# dogs102_3_3v_v0_5.net
KiCad netlist of a schematic drawn in EAGLE
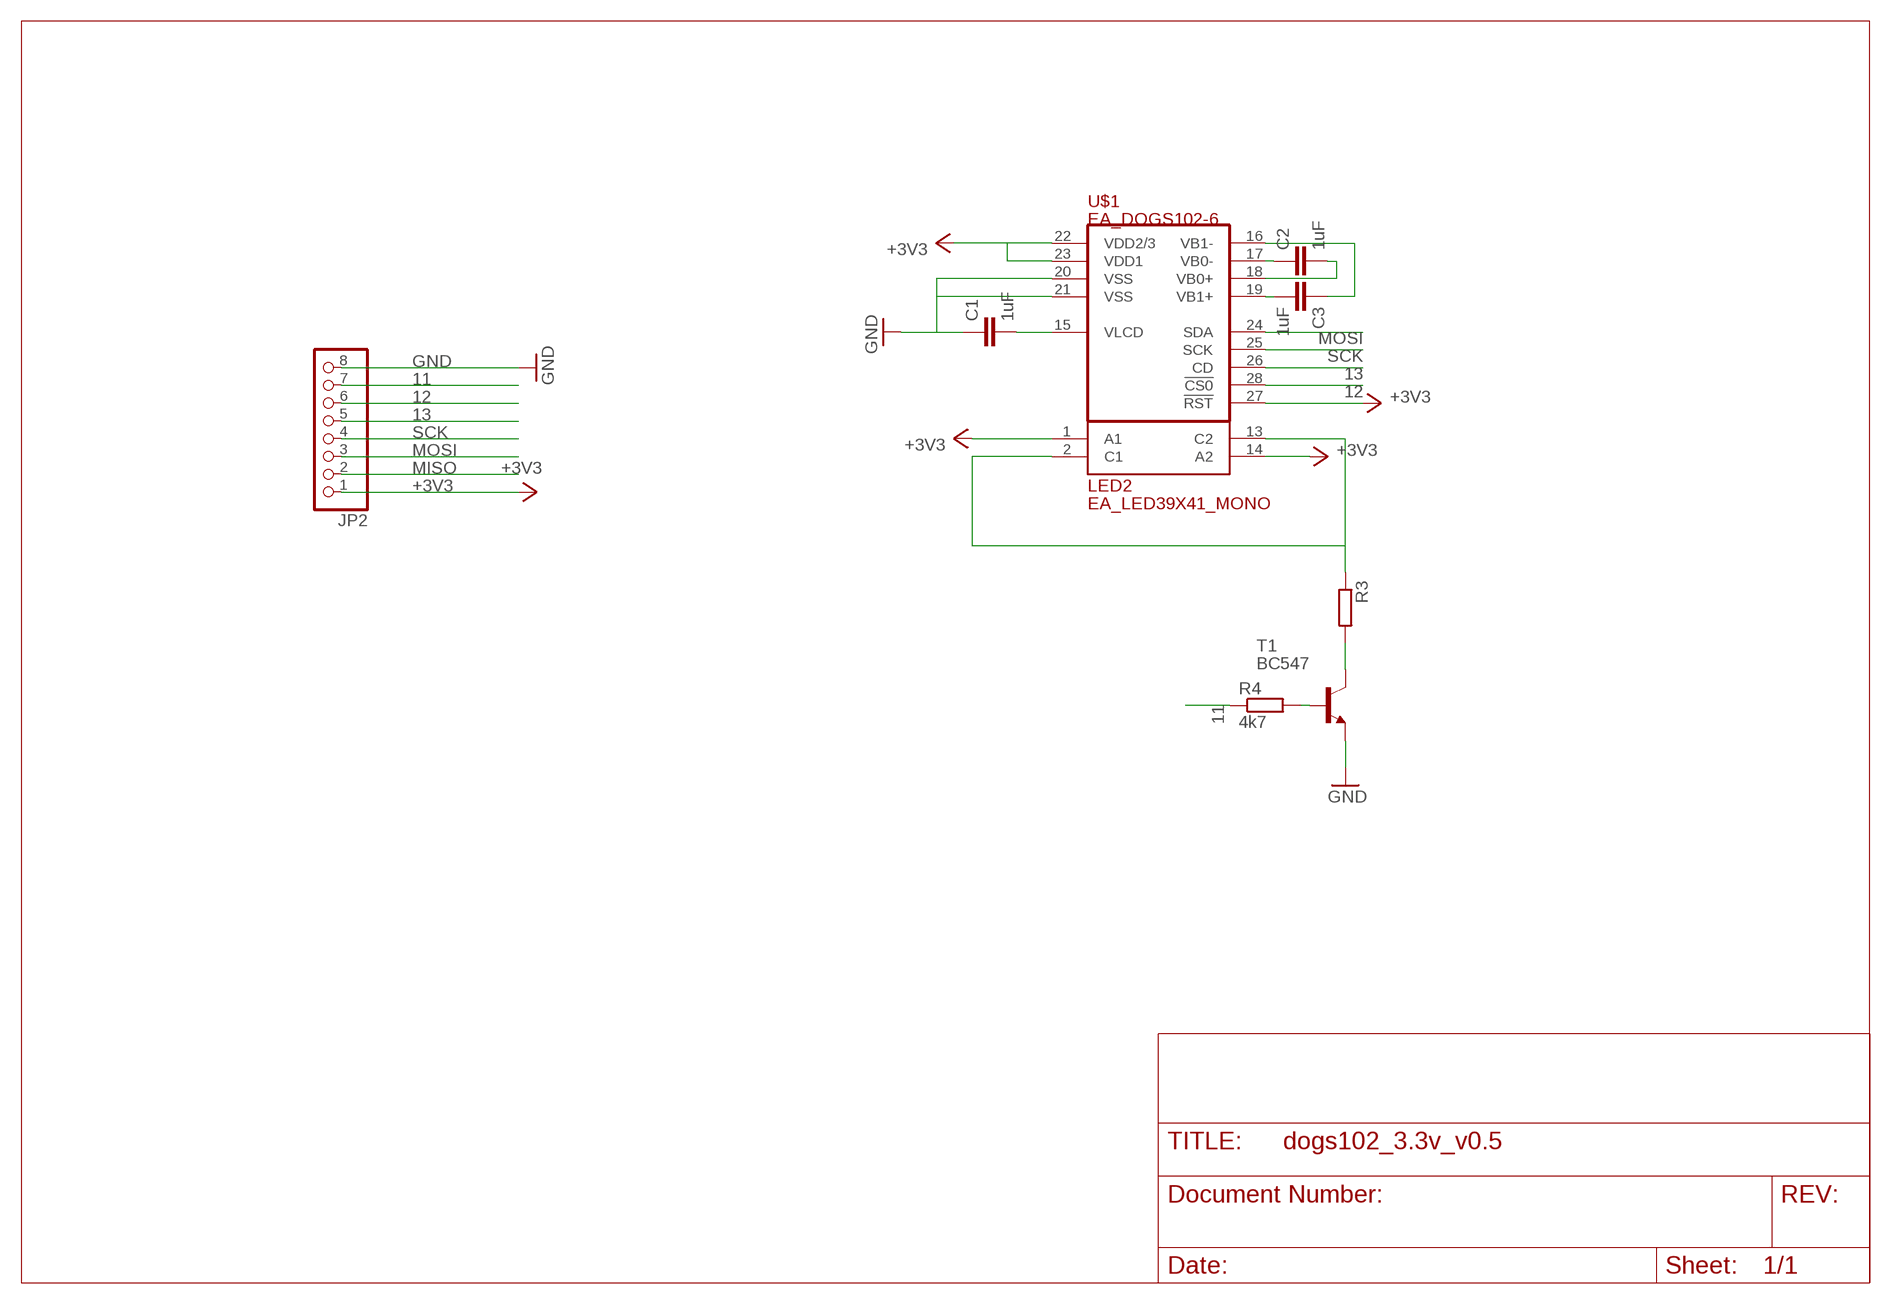
[diagram p0: schematic, sheet 1]

(export (version "E")
  (design (tool "Eeschema 10.0.6"))
  (components
    (comp (ref "C1")
      (value "1uF")
      (footprint "eagle-import:C050-035X075")
      (libsource (lib "eagle-import") (part "C-EU050-035X075"))
    )
    (comp (ref "C2")
      (value "1uF")
      (footprint "eagle-import:C050-035X075")
      (libsource (lib "eagle-import") (part "C-EU050-035X075"))
    )
    (comp (ref "C3")
      (value "1uF")
      (footprint "eagle-import:C050-035X075")
      (libsource (lib "eagle-import") (part "C-EU050-035X075"))
    )
    (comp (ref "JP2")
      (value "PINHD-1X8")
      (footprint "eagle-import:1X08")
      (libsource (lib "eagle-import") (part "PINHD-1X8"))
    )
    (comp (ref "LED2")
      (value "EA_LED39X41_MONO")
      (footprint "eagle-import:EA_LED39X41")
      (libsource (lib "eagle-import") (part "EA_LED39X41_MONO"))
    )
    (comp (ref "R3")
      (value "R-EU_0204/2V")
      (footprint "eagle-import:0204V")
      (libsource (lib "eagle-import") (part "R-EU_0204/2V"))
    )
    (comp (ref "R4")
      (value "4k7")
      (footprint "eagle-import:0204V")
      (libsource (lib "eagle-import") (part "R-EU_0204/2V"))
    )
    (comp (ref "T1")
      (value "BC547")
      (footprint "eagle-import:TO92-CBE")
      (libsource (lib "eagle-import") (part "-NPN-TO92-CBEBC547"))
    )
    (comp (ref "U$1")
      (value "EA_DOGS102-6")
      (footprint "eagle-import:EA_DOGS102-6")
      (libsource (lib "eagle-import") (part "EA_DOGS102-6"))
    )
  )
  (nets
    (net (code "1") (name "+3V3") (class "Default")
      (node (ref "JP2") (pin "1") (pinfunction "1_1") (pintype "passive"))
      (node (ref "LED2") (pin "1") (pinfunction "A1_1") (pintype "passive"))
      (node (ref "LED2") (pin "14") (pinfunction "A2_14") (pintype "passive"))
      (node (ref "U$1") (pin "22") (pinfunction "VDD2/3_22") (pintype "power_in"))
      (node (ref "U$1") (pin "23") (pinfunction "VDD1_23") (pintype "power_in"))
      (node (ref "U$1") (pin "27") (pinfunction "~{RST}_27") (pintype "input"))
    )
    (net (code "2") (name "/11") (class "Default")
      (node (ref "JP2") (pin "7") (pinfunction "7_7") (pintype "passive"))
      (node (ref "R4") (pin "1") (pinfunction "1_1") (pintype "passive"))
    )
    (net (code "3") (name "/12") (class "Default")
      (node (ref "JP2") (pin "6") (pinfunction "6_6") (pintype "passive"))
      (node (ref "U$1") (pin "28") (pinfunction "~{CS0}_28") (pintype "input"))
    )
    (net (code "4") (name "/13") (class "Default")
      (node (ref "JP2") (pin "5") (pinfunction "5_5") (pintype "passive"))
      (node (ref "U$1") (pin "26") (pinfunction "CD_26") (pintype "bidirectional"))
    )
    (net (code "5") (name "/MISO") (class "Default")
      (node (ref "JP2") (pin "2") (pinfunction "2_2") (pintype "passive"))
    )
    (net (code "6") (name "/MOSI") (class "Default")
      (node (ref "JP2") (pin "3") (pinfunction "3_3") (pintype "passive"))
      (node (ref "U$1") (pin "24") (pinfunction "SDA_24") (pintype "bidirectional"))
    )
    (net (code "7") (name "/SCK") (class "Default")
      (node (ref "JP2") (pin "4") (pinfunction "4_4") (pintype "passive"))
      (node (ref "U$1") (pin "25") (pinfunction "SCK_25") (pintype "input"))
    )
    (net (code "8") (name "GND") (class "Default")
      (node (ref "C1") (pin "1") (pinfunction "1_1") (pintype "passive"))
      (node (ref "JP2") (pin "8") (pinfunction "8_8") (pintype "passive"))
      (node (ref "T1") (pin "E") (pinfunction "E_E") (pintype "passive"))
      (node (ref "U$1") (pin "20") (pinfunction "VSS_20") (pintype "bidirectional"))
      (node (ref "U$1") (pin "21") (pinfunction "VSS_21") (pintype "bidirectional"))
    )
    (net (code "9") (name "Net-(LED2-C1)") (class "Default")
      (node (ref "LED2") (pin "13") (pinfunction "C2_13") (pintype "passive"))
      (node (ref "LED2") (pin "2") (pinfunction "C1_2") (pintype "passive"))
      (node (ref "R3") (pin "1") (pinfunction "1_1") (pintype "passive"))
    )
    (net (code "10") (name "Net-(R3-Pad2)") (class "Default")
      (node (ref "R3") (pin "2") (pinfunction "2_2") (pintype "passive"))
      (node (ref "T1") (pin "C") (pinfunction "C_C") (pintype "passive"))
    )
    (net (code "11") (name "Net-(R4-Pad2)") (class "Default")
      (node (ref "R4") (pin "2") (pinfunction "2_2") (pintype "passive"))
      (node (ref "T1") (pin "B") (pinfunction "B_B") (pintype "passive"))
    )
    (net (code "12") (name "Net-(U$1-VB0+)") (class "Default")
      (node (ref "C2") (pin "2") (pinfunction "2_2") (pintype "passive"))
      (node (ref "U$1") (pin "18") (pinfunction "VB0+_18") (pintype "bidirectional"))
    )
    (net (code "13") (name "Net-(U$1-VB0-)") (class "Default")
      (node (ref "C2") (pin "1") (pinfunction "1_1") (pintype "passive"))
      (node (ref "U$1") (pin "17") (pinfunction "VB0-_17") (pintype "bidirectional"))
    )
    (net (code "14") (name "Net-(U$1-VB1+)") (class "Default")
      (node (ref "C3") (pin "2") (pinfunction "2_2") (pintype "passive"))
      (node (ref "U$1") (pin "19") (pinfunction "VB1+_19") (pintype "bidirectional"))
    )
    (net (code "15") (name "Net-(U$1-VB1-)") (class "Default")
      (node (ref "C3") (pin "1") (pinfunction "1_1") (pintype "passive"))
      (node (ref "U$1") (pin "16") (pinfunction "VB1-_16") (pintype "bidirectional"))
    )
    (net (code "16") (name "Net-(U$1-VLCD)") (class "Default")
      (node (ref "C1") (pin "2") (pinfunction "2_2") (pintype "passive"))
      (node (ref "U$1") (pin "15") (pinfunction "VLCD_15") (pintype "bidirectional"))
    )
  )
)
